# Snap4.net
KiCad netlist of a schematic drawn in Altium Designer
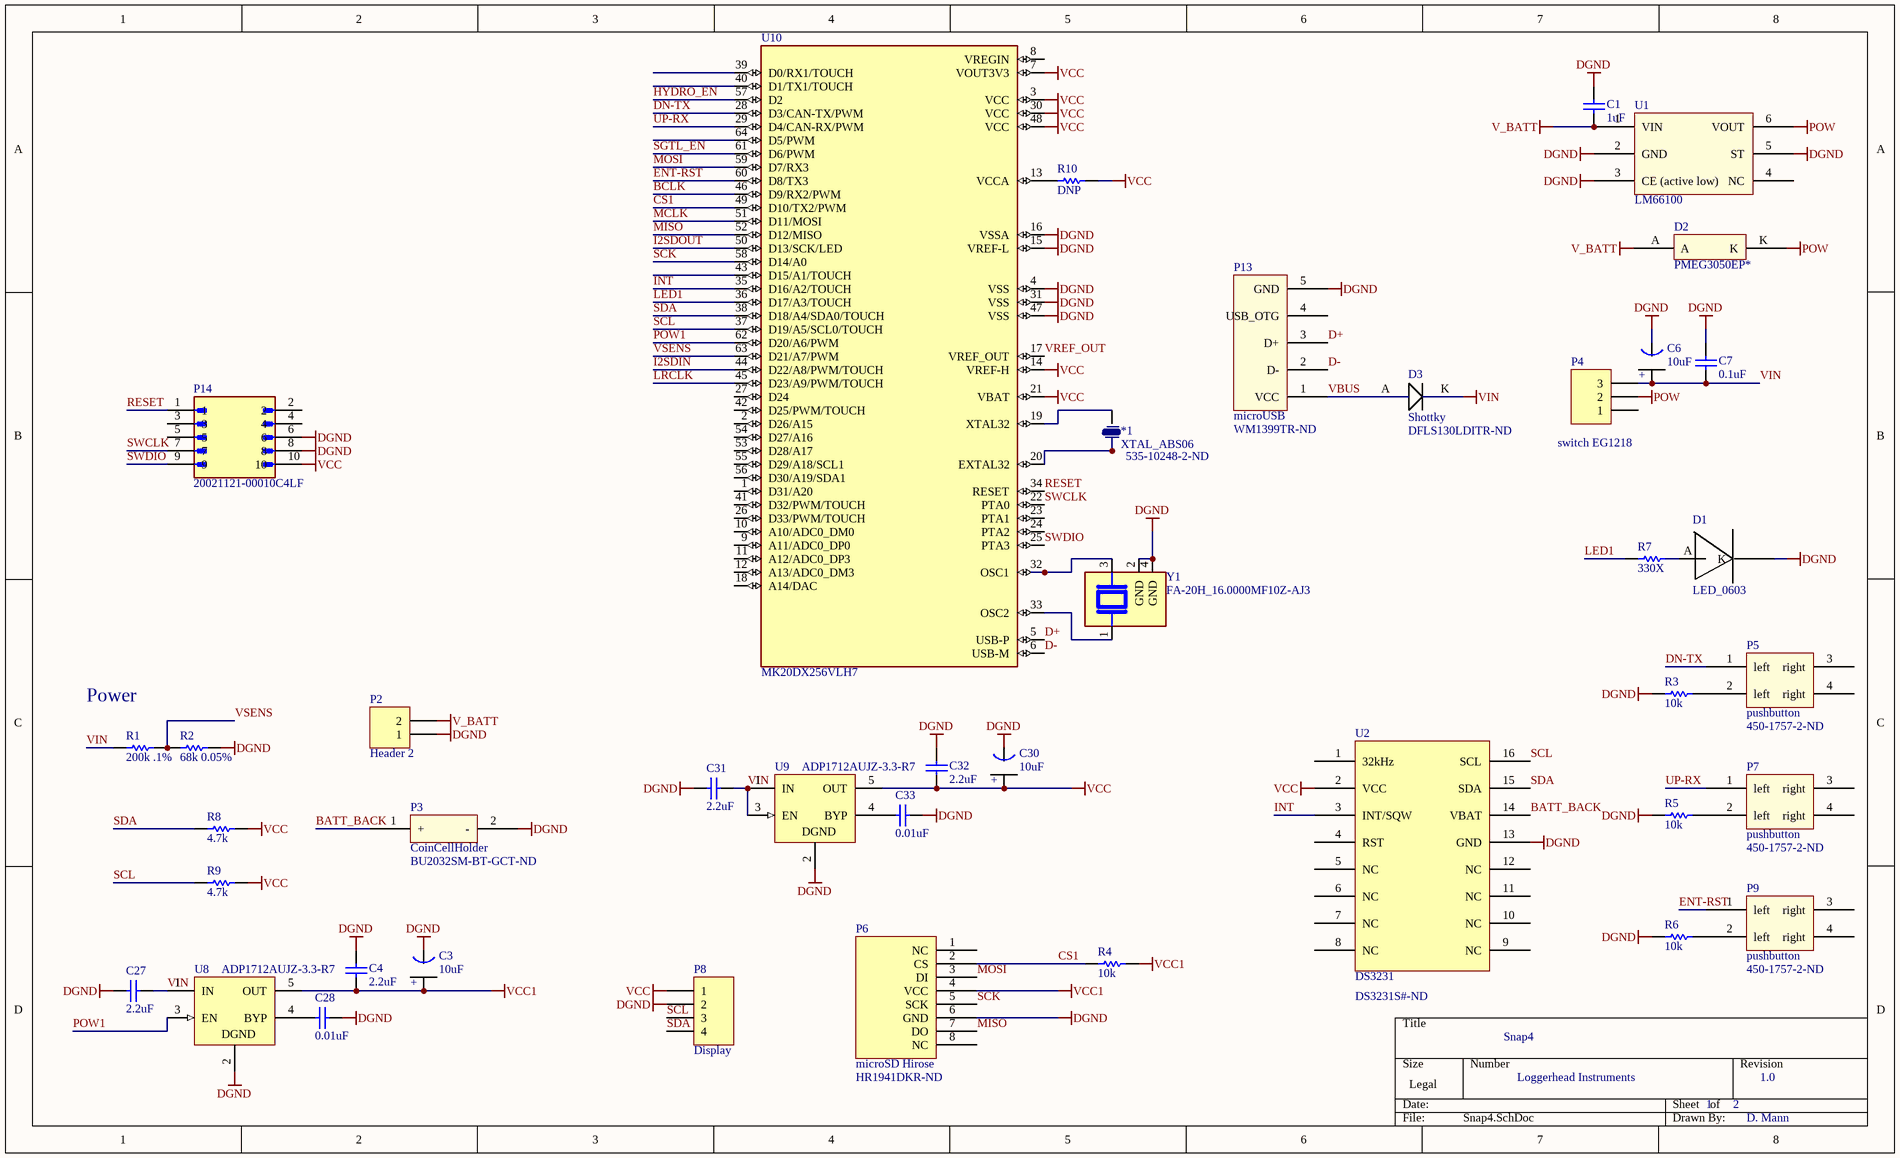
[diagram p0: Snap4.SchDoc]

(export (version "E")
  (design (tool "Eeschema 10.0.6"))
  (components
    (comp (ref "*1")
      (value "XTAL_ABS06")
      (footprint "XTAL-ABS06")
      (fields (field (name "SUPPLIER PART NUMBER 1") "535-10248-2-ND"))
      (libsource (lib "Loggerhead") (part "XTAL_ABS06"))
    )
    (comp (ref "C1")
      (value "1uF")
      (footprint "0402")
      (description "Ceramic Chip Capacitor - Standard")
      (fields (field (name "PUBLISHER") "Altium Limited"))
      (libsource (lib "KEMET Chip Capacitor") (part "C0402"))
    )
    (comp (ref "C3") (value "10uF") (footprint "Tant0805") (libsource (lib "Loggerhead") (part "Tant0805")))
    (comp (ref "C4")
      (value "2.2uF")
      (footprint "0402")
      (description "Ceramic Chip Capacitor - Standard")
      (fields (field (name "PUBLISHER") "Altium Limited"))
      (libsource (lib "KEMET Chip Capacitor") (part "C0402"))
    )
    (comp (ref "C6") (value "10uF") (footprint "Tant0805") (libsource (lib "Loggerhead") (part "Tant0805")))
    (comp (ref "C7")
      (value "0.1uF")
      (footprint "0402")
      (description "Ceramic Chip Capacitor - Standard")
      (fields (field (name "PUBLISHER") "Altium Limited"))
      (libsource (lib "KEMET Chip Capacitor") (part "C0402"))
    )
    (comp (ref "C27")
      (value "2.2uF")
      (footprint "0402")
      (description "Ceramic Chip Capacitor - Standard")
      (fields (field (name "PUBLISHER") "Altium Limited"))
      (libsource (lib "KEMET Chip Capacitor") (part "C0402"))
    )
    (comp (ref "C28")
      (value "0.01uF")
      (footprint "0402")
      (description "Ceramic Chip Capacitor - Standard")
      (fields (field (name "PUBLISHER") "Altium Limited"))
      (libsource (lib "KEMET Chip Capacitor") (part "C0402"))
    )
    (comp (ref "C30") (value "10uF") (footprint "Tant0805") (libsource (lib "Loggerhead") (part "Tant0805")))
    (comp (ref "C31")
      (value "2.2uF")
      (footprint "0402")
      (description "Ceramic Chip Capacitor - Standard")
      (fields (field (name "PUBLISHER") "Altium Limited"))
      (libsource (lib "KEMET Chip Capacitor") (part "C0402"))
    )
    (comp (ref "C32")
      (value "2.2uF")
      (footprint "0402")
      (description "Ceramic Chip Capacitor - Standard")
      (fields (field (name "PUBLISHER") "Altium Limited"))
      (libsource (lib "KEMET Chip Capacitor") (part "C0402"))
    )
    (comp (ref "C33")
      (value "0.01uF")
      (footprint "0402")
      (description "Ceramic Chip Capacitor - Standard")
      (fields (field (name "PUBLISHER") "Altium Limited"))
      (libsource (lib "KEMET Chip Capacitor") (part "C0402"))
    )
    (comp (ref "D1")
      (value "LED_0603")
      (footprint "Diode0603")
      (libsource (lib "Loggerhead") (part "LED_0603"))
    )
    (comp (ref "D2")
      (value "PMEG3050EP*")
      (footprint "Diode_PMEG3050EP")
      (libsource (lib "Loggerhead") (part "Diode_PMEG3050EP"))
    )
    (comp (ref "D3")
      (value "Shottky")
      (footprint "DFLS130")
      (fields (field (name "SUPPLIER PART NUMBER 1") "DFLS130LDITR-ND"))
      (libsource (lib "Loggerhead") (part "DFLS130"))
    )
    (comp (ref "P2")
      (value "Header 2")
      (footprint "HDR1X2")
      (description "Header, 2-Pin")
      (fields (field (name "PUBLISHER") "Altium Limited"))
      (libsource (lib "Miscellaneous Connectors") (part "Header 2"))
    )
    (comp (ref "P3")
      (value "CoinCellHolder")
      (footprint "CoinCellHolder")
      (fields (field (name "SUPPLIER PART NUMBER 1") "BU2032SM-BT-GCT-ND"))
      (libsource (lib "Loggerhead") (part "CoinCellHolder"))
    )
    (comp (ref "P4")
      (value "switch EG1218")
      (footprint "HDR1X3")
      (description "Header, 3-Pin")
      (fields (field (name "PUBLISHER") "Altium Limited"))
      (libsource (lib "Miscellaneous Connectors") (part "Header 3"))
    )
    (comp (ref "P5")
      (value "pushbutton")
      (footprint "SOP4")
      (fields (field (name "SUPPLIER PART NUMBER 1") "450-1757-2-ND"))
      (libsource (lib "Loggerhead") (part "pushbutton"))
    )
    (comp (ref "P6")
      (value "microSD Hirose")
      (footprint "DM3D microSD")
      (fields (field (name "SUPPLIER PART NUMBER 1") "HR1941DKR-ND"))
      (libsource (lib "Loggerhead") (part "microSD Hirose"))
    )
    (comp (ref "P7")
      (value "pushbutton")
      (footprint "SOP4")
      (fields (field (name "SUPPLIER PART NUMBER 1") "450-1757-2-ND"))
      (libsource (lib "Loggerhead") (part "pushbutton"))
    )
    (comp (ref "P8")
      (value "Display")
      (footprint "HDR1X4")
      (description "Header, 4-Pin")
      (fields (field (name "PUBLISHER") "Altium Limited"))
      (libsource (lib "Miscellaneous Connectors") (part "Header 4"))
    )
    (comp (ref "P9")
      (value "pushbutton")
      (footprint "SOP4")
      (fields (field (name "SUPPLIER PART NUMBER 1") "450-1757-2-ND"))
      (libsource (lib "Loggerhead") (part "pushbutton"))
    )
    (comp (ref "P13")
      (value "microUSB")
      (footprint "microUSB-B")
      (fields (field (name "SUPPLIER PART NUMBER 1") "WM1399TR-ND"))
      (libsource (lib "Loggerhead") (part "microUSB-B"))
    )
    (comp (ref "P14")
      (value "20021121-00010C4LF")
      (footprint "AMPHENOL_20021121-00010C4LF")
      (fields (field (name "MF") "Amphenol ICC"))
      (libsource (lib "cortex_20021121-00010C4LF") (part "20021121-00010C4LF"))
    )
    (comp (ref "R1")
      (value "200k .1%")
      (footprint "3-0603")
      (fields (field (name "PUBLISHER") "Altium Limited"))
      (libsource (lib "Panasonic Resistor") (part "ERJ3RK"))
    )
    (comp (ref "R2")
      (value "68k 0.05%")
      (footprint "3-0603")
      (fields (field (name "PUBLISHER") "Altium Limited"))
      (libsource (lib "Panasonic Resistor") (part "ERJ3RK"))
    )
    (comp (ref "R3")
      (value "10k")
      (footprint "3-0603")
      (fields (field (name "PUBLISHER") "Altium Limited"))
      (libsource (lib "Panasonic Resistor") (part "ERJ3RK"))
    )
    (comp (ref "R4")
      (value "10k")
      (footprint "3-0603")
      (fields (field (name "PUBLISHER") "Altium Limited"))
      (libsource (lib "Panasonic Resistor") (part "ERJ3RK"))
    )
    (comp (ref "R5")
      (value "10k")
      (footprint "3-0603")
      (fields (field (name "PUBLISHER") "Altium Limited"))
      (libsource (lib "Panasonic Resistor") (part "ERJ3RK"))
    )
    (comp (ref "R6")
      (value "10k")
      (footprint "3-0603")
      (fields (field (name "PUBLISHER") "Altium Limited"))
      (libsource (lib "Panasonic Resistor") (part "ERJ3RK"))
    )
    (comp (ref "R7")
      (value "330X")
      (footprint "3-0603")
      (fields (field (name "PUBLISHER") "Altium Limited"))
      (libsource (lib "Panasonic Resistor") (part "ERJ3RK"))
    )
    (comp (ref "R8")
      (value "4.7k")
      (footprint "3-0603")
      (fields (field (name "PUBLISHER") "Altium Limited"))
      (libsource (lib "Panasonic Resistor") (part "ERJ3RK"))
    )
    (comp (ref "R9")
      (value "4.7k")
      (footprint "3-0603")
      (fields (field (name "PUBLISHER") "Altium Limited"))
      (libsource (lib "Panasonic Resistor") (part "ERJ3RK"))
    )
    (comp (ref "R10")
      (value "DNP")
      (footprint "3-0603")
      (fields (field (name "PUBLISHER") "Altium Limited"))
      (libsource (lib "Panasonic Resistor") (part "ERJ3RK"))
    )
    (comp (ref "U1") (value "LM66100") (footprint "SC-70-6") (libsource (lib "Loggerhead") (part "LM66100")))
    (comp (ref "U2")
      (value "DS3231")
      (footprint "DS3231")
      (fields (field (name "SUPPLIER PART NUMBER 1") "DS3231S#-ND"))
      (libsource (lib "Loggerhead") (part "DS3231"))
    )
    (comp (ref "U8")
      (value "ADP1712AUJZ-3.3-R7")
      (footprint "MF05A_N")
      (description "Micropower, 150mA Low-Noise Ultra Low-Dropout CMOS Voltage Regulator")
      (fields
        (field (name "PARTNUMBER") "LP3985IM5-3.3")
        (field (name "MANUFACTURER") "National Semiconductor")
        (field (name "PUBLISHER") "Altium Limited")
      )
      (libsource (lib "NSC LDO") (part "LP3985IM5-3.3"))
    )
    (comp (ref "U9")
      (value "ADP1712AUJZ-3.3-R7")
      (footprint "MF05A_N")
      (description "Micropower, 150mA Low-Noise Ultra Low-Dropout CMOS Voltage Regulator")
      (fields
        (field (name "PARTNUMBER") "LP3985IM5-3.3")
        (field (name "MANUFACTURER") "National Semiconductor")
        (field (name "PUBLISHER") "Altium Limited")
      )
      (libsource (lib "NSC LDO") (part "LP3985IM5-3.3"))
    )
    (comp (ref "U10")
      (value "MK20DX256VLH7")
      (footprint "QFP50P1200X1200X160-64N")
      (description "ARMÂ®CortexÂ®-M4Kinetis K20å¾®æŽ§åˆ¶å™¨IC 32ä½72MHz 256KBï¼ˆ256K x 8ï¼‰FLASH 64-LQFPï¼ˆ10x10ï¼‰")
      (fields (field (name "MF") "NXP USA"))
      (libsource (lib "MK20DX256VLH7") (part "MK20DX256VLH7"))
    )
    (comp (ref "Y1")
      (value "FA-20H_16.0000MF10Z-AJ3")
      (footprint "XTAL_FA-20H_16.0000MF10Z-AJ3")
      (description "16 MHz ±10ppm Crystal 8pF 80 Ohms 4-SMD, No Lead")
      (fields (field (name "MF") "EPSON") (field (name "MP") "FA-20H 16.0000MF10Z-AJ3"))
      (libsource (lib "FA-20H_16.0000MF10Z-AJ3") (part "FA-20H_16.0000MF10Z-AJ3"))
    )
  )
  (nets
    (net (code "1") (name "/BATT_BACK") (class "Default")
      (node (ref "P3") (pin "1") (pinfunction "+_1") (pintype "passive"))
      (node (ref "U2") (pin "14") (pinfunction "VBAT_14") (pintype "power_in"))
    )
    (net (code "2") (name "/BCLK") (class "Default")
      (node (ref "U10") (pin "46") (pinfunction "D9/RX2/PWM_46") (pintype "bidirectional"))
    )
    (net (code "3") (name "/CS1") (class "Default")
      (node (ref "P6") (pin "2") (pinfunction "CS_2") (pintype "passive"))
      (node (ref "R4") (pin "2") (pinfunction "2_2") (pintype "passive"))
      (node (ref "U10") (pin "49") (pinfunction "D10/TX2/PWM_49") (pintype "bidirectional"))
    )
    (net (code "4") (name "/D+") (class "Default")
      (node (ref "P13") (pin "3") (pinfunction "D+_3") (pintype "passive"))
      (node (ref "U10") (pin "5") (pinfunction "USB-P_5") (pintype "bidirectional"))
    )
    (net (code "5") (name "/D-") (class "Default")
      (node (ref "P13") (pin "2") (pinfunction "D-_2") (pintype "passive"))
      (node (ref "U10") (pin "6") (pinfunction "USB-M_6") (pintype "bidirectional"))
    )
    (net (code "6") (name "/DN-TX") (class "Default")
      (node (ref "P5") (pin "1") (pinfunction "left_1") (pintype "passive"))
      (node (ref "U10") (pin "28") (pinfunction "D3/CAN-TX/PWM_28") (pintype "bidirectional"))
    )
    (net (code "7") (name "/ENT-RST") (class "Default")
      (node (ref "P9") (pin "1") (pinfunction "left_1") (pintype "passive"))
      (node (ref "U10") (pin "60") (pinfunction "D8/TX3_60") (pintype "bidirectional"))
    )
    (net (code "8") (name "/HYDRO_EN") (class "Default")
      (node (ref "U10") (pin "57") (pinfunction "D2_57") (pintype "bidirectional"))
    )
    (net (code "9") (name "/I2SDIN") (class "Default")
      (node (ref "U10") (pin "44") (pinfunction "D22/A8/PWM/TOUCH_44") (pintype "bidirectional"))
    )
    (net (code "10") (name "/I2SDOUT") (class "Default")
      (node (ref "U10") (pin "50") (pinfunction "D13/SCK/LED_50") (pintype "bidirectional"))
    )
    (net (code "11") (name "/INT") (class "Default")
      (node (ref "U10") (pin "35") (pinfunction "D16/A2/TOUCH_35") (pintype "bidirectional"))
      (node (ref "U2") (pin "3") (pinfunction "INT/SQW_3") (pintype "passive"))
    )
    (net (code "12") (name "/LED1") (class "Default")
      (node (ref "R7") (pin "1") (pinfunction "1_1") (pintype "passive"))
      (node (ref "U10") (pin "36") (pinfunction "D17/A3/TOUCH_36") (pintype "bidirectional"))
    )
    (net (code "13") (name "/LRCLK") (class "Default")
      (node (ref "U10") (pin "45") (pinfunction "D23/A9/PWM/TOUCH_45") (pintype "bidirectional"))
    )
    (net (code "14") (name "/MCLK") (class "Default")
      (node (ref "U10") (pin "51") (pinfunction "D11/MOSI_51") (pintype "bidirectional"))
    )
    (net (code "15") (name "/MISO") (class "Default")
      (node (ref "P6") (pin "7") (pinfunction "DO_7") (pintype "passive"))
      (node (ref "U10") (pin "52") (pinfunction "D12/MISO_52") (pintype "bidirectional"))
    )
    (net (code "16") (name "/MOSI") (class "Default")
      (node (ref "P6") (pin "3") (pinfunction "DI_3") (pintype "passive"))
      (node (ref "U10") (pin "59") (pinfunction "D7/RX3_59") (pintype "bidirectional"))
    )
    (net (code "17") (name "/POW1") (class "Default")
      (node (ref "U10") (pin "62") (pinfunction "D20/A6/PWM_62") (pintype "bidirectional"))
      (node (ref "U8") (pin "3") (pinfunction "EN_3") (pintype "input"))
    )
    (net (code "18") (name "/RESET") (class "Default")
      (node (ref "P14") (pin "1") (pinfunction "1_1") (pintype "passive"))
      (node (ref "U10") (pin "34") (pinfunction "RESET_34") (pintype "bidirectional"))
    )
    (net (code "19") (name "/SCK") (class "Default")
      (node (ref "P6") (pin "5") (pinfunction "SCK_5") (pintype "passive"))
      (node (ref "U10") (pin "58") (pinfunction "D14/A0_58") (pintype "bidirectional"))
    )
    (net (code "20") (name "/SCL") (class "Default")
      (node (ref "P8") (pin "3") (pinfunction "3_3") (pintype "passive"))
      (node (ref "R9") (pin "1") (pinfunction "1_1") (pintype "passive"))
      (node (ref "U10") (pin "37") (pinfunction "D19/A5/SCL0/TOUCH_37") (pintype "bidirectional"))
      (node (ref "U2") (pin "16") (pinfunction "SCL_16") (pintype "passive"))
    )
    (net (code "21") (name "/SDA") (class "Default")
      (node (ref "P8") (pin "4") (pinfunction "4_4") (pintype "passive"))
      (node (ref "R8") (pin "1") (pinfunction "1_1") (pintype "passive"))
      (node (ref "U10") (pin "38") (pinfunction "D18/A4/SDA0/TOUCH_38") (pintype "bidirectional"))
      (node (ref "U2") (pin "15") (pinfunction "SDA_15") (pintype "passive"))
    )
    (net (code "22") (name "/SGTL_EN") (class "Default")
      (node (ref "U10") (pin "61") (pinfunction "D6/PWM_61") (pintype "bidirectional"))
    )
    (net (code "23") (name "/SWCLK") (class "Default")
      (node (ref "P14") (pin "7") (pinfunction "7_7") (pintype "passive"))
      (node (ref "U10") (pin "22") (pinfunction "PTA0_22") (pintype "bidirectional"))
    )
    (net (code "24") (name "/SWDIO") (class "Default")
      (node (ref "P14") (pin "9") (pinfunction "9_9") (pintype "passive"))
      (node (ref "U10") (pin "25") (pinfunction "PTA3_25") (pintype "bidirectional"))
    )
    (net (code "25") (name "/UP-RX") (class "Default")
      (node (ref "P7") (pin "1") (pinfunction "left_1") (pintype "passive"))
      (node (ref "U10") (pin "29") (pinfunction "D4/CAN-RX/PWM_29") (pintype "bidirectional"))
    )
    (net (code "26") (name "/VBUS") (class "Default")
      (node (ref "D3") (pin "A") (pintype "passive"))
      (node (ref "P13") (pin "1") (pinfunction "VCC_1") (pintype "passive"))
    )
    (net (code "27") (name "/VREF_OUT") (class "Default")
      (node (ref "U10") (pin "17") (pinfunction "VREF_OUT_17") (pintype "bidirectional"))
    )
    (net (code "28") (name "/VSENS") (class "Default")
      (node (ref "R1") (pin "1") (pinfunction "1_1") (pintype "passive"))
      (node (ref "R2") (pin "2") (pinfunction "2_2") (pintype "passive"))
      (node (ref "U10") (pin "63") (pinfunction "D21/A7/PWM_63") (pintype "bidirectional"))
    )
    (net (code "29") (name "DGND") (class "Default")
      (node (ref "C1") (pin "1") (pinfunction "1_1") (pintype "passive"))
      (node (ref "C27") (pin "2") (pinfunction "2_2") (pintype "passive"))
      (node (ref "C28") (pin "2") (pinfunction "2_2") (pintype "passive"))
      (node (ref "C3") (pin "1") (pinfunction "GND_1") (pintype "passive"))
      (node (ref "C30") (pin "1") (pinfunction "GND_1") (pintype "passive"))
      (node (ref "C31") (pin "2") (pinfunction "2_2") (pintype "passive"))
      (node (ref "C32") (pin "2") (pinfunction "2_2") (pintype "passive"))
      (node (ref "C33") (pin "2") (pinfunction "2_2") (pintype "passive"))
      (node (ref "C4") (pin "2") (pinfunction "2_2") (pintype "passive"))
      (node (ref "C6") (pin "1") (pinfunction "GND_1") (pintype "passive"))
      (node (ref "C7") (pin "2") (pinfunction "2_2") (pintype "passive"))
      (node (ref "D1") (pin "K") (pinfunction "K_K") (pintype "passive"))
      (node (ref "P13") (pin "5") (pinfunction "GND_5") (pintype "passive"))
      (node (ref "P14") (pin "6") (pinfunction "6_6") (pintype "passive"))
      (node (ref "P14") (pin "8") (pinfunction "8_8") (pintype "passive"))
      (node (ref "P2") (pin "1") (pinfunction "1_1") (pintype "passive"))
      (node (ref "P3") (pin "2") (pinfunction "-_2") (pintype "passive"))
      (node (ref "P6") (pin "6") (pinfunction "GND_6") (pintype "passive"))
      (node (ref "P8") (pin "2") (pinfunction "2_2") (pintype "passive"))
      (node (ref "R2") (pin "1") (pinfunction "1_1") (pintype "passive"))
      (node (ref "R3") (pin "2") (pinfunction "2_2") (pintype "passive"))
      (node (ref "R5") (pin "2") (pinfunction "2_2") (pintype "passive"))
      (node (ref "R6") (pin "2") (pinfunction "2_2") (pintype "passive"))
      (node (ref "U1") (pin "2") (pinfunction "GND_2") (pintype "passive"))
      (node (ref "U1") (pin "3") (pinfunction "CE_(active_low)_3") (pintype "passive"))
      (node (ref "U1") (pin "5") (pinfunction "ST_5") (pintype "passive"))
      (node (ref "U10") (pin "15") (pinfunction "VREF-L_15") (pintype "bidirectional"))
      (node (ref "U10") (pin "16") (pinfunction "VSSA_16") (pintype "bidirectional"))
      (node (ref "U10") (pin "31") (pinfunction "VSS_31") (pintype "bidirectional"))
      (node (ref "U10") (pin "4") (pinfunction "VSS_4") (pintype "bidirectional"))
      (node (ref "U10") (pin "47") (pinfunction "VSS_47") (pintype "bidirectional"))
      (node (ref "U2") (pin "13") (pinfunction "GND_13") (pintype "passive"))
      (node (ref "U8") (pin "2") (pinfunction "GND_2") (pintype "power_in"))
      (node (ref "U9") (pin "2") (pinfunction "GND_2") (pintype "power_in"))
      (node (ref "Y1") (pin "2") (pinfunction "GND_2") (pintype "power_in"))
      (node (ref "Y1") (pin "4") (pinfunction "GND_4") (pintype "power_in"))
    )
    (net (code "30") (name "Net-(D1-PadA)") (class "Default")
      (node (ref "D1") (pin "A") (pinfunction "A_A") (pintype "passive"))
      (node (ref "R7") (pin "2") (pinfunction "2_2") (pintype "passive"))
    )
    (net (code "31") (name "Net-(P5-left-Pad2)") (class "Default")
      (node (ref "P5") (pin "2") (pinfunction "left_2") (pintype "passive"))
      (node (ref "R3") (pin "1") (pinfunction "1_1") (pintype "passive"))
    )
    (net (code "32") (name "Net-(P7-left-Pad2)") (class "Default")
      (node (ref "P7") (pin "2") (pinfunction "left_2") (pintype "passive"))
      (node (ref "R5") (pin "1") (pinfunction "1_1") (pintype "passive"))
    )
    (net (code "33") (name "Net-(P9-left-Pad2)") (class "Default")
      (node (ref "P9") (pin "2") (pinfunction "left_2") (pintype "passive"))
      (node (ref "R6") (pin "1") (pinfunction "1_1") (pintype "passive"))
    )
    (net (code "34") (name "Net-(U8-BYP)") (class "Default")
      (node (ref "C28") (pin "1") (pinfunction "1_1") (pintype "passive"))
      (node (ref "U8") (pin "4") (pinfunction "BYP_4") (pintype "passive"))
    )
    (net (code "35") (name "Net-(U9-BYP)") (class "Default")
      (node (ref "C33") (pin "1") (pinfunction "1_1") (pintype "passive"))
      (node (ref "U9") (pin "4") (pinfunction "BYP_4") (pintype "passive"))
    )
    (net (code "36") (name "Net-(U10-EXTAL32)") (class "Default")
      (node (ref "*1") (pin "1") (pinfunction "1_1") (pintype "passive"))
      (node (ref "U10") (pin "20") (pinfunction "EXTAL32_20") (pintype "bidirectional"))
    )
    (net (code "37") (name "Net-(U10-OSC1)") (class "Default")
      (node (ref "U10") (pin "32") (pinfunction "OSC1_32") (pintype "bidirectional"))
      (node (ref "Y1") (pin "3") (pinfunction "2_3") (pintype "passive"))
    )
    (net (code "38") (name "Net-(U10-OSC2)") (class "Default")
      (node (ref "U10") (pin "33") (pinfunction "OSC2_33") (pintype "bidirectional"))
      (node (ref "Y1") (pin "1") (pinfunction "1_1") (pintype "passive"))
    )
    (net (code "39") (name "Net-(U10-VCCA)") (class "Default")
      (node (ref "R10") (pin "1") (pinfunction "1_1") (pintype "passive"))
      (node (ref "U10") (pin "13") (pinfunction "VCCA_13") (pintype "bidirectional"))
    )
    (net (code "40") (name "Net-(U10-XTAL32)") (class "Default")
      (node (ref "*1") (pin "2") (pinfunction "2_2") (pintype "passive"))
      (node (ref "U10") (pin "19") (pinfunction "XTAL32_19") (pintype "bidirectional"))
    )
    (net (code "41") (name "POW") (class "Default")
      (node (ref "D2") (pin "K") (pinfunction "K_K") (pintype "passive"))
      (node (ref "P4") (pin "2") (pinfunction "2_2") (pintype "passive"))
      (node (ref "U1") (pin "6") (pinfunction "VOUT_6") (pintype "passive"))
    )
    (net (code "42") (name "VCC") (class "Default")
      (node (ref "C30") (pin "2") (pinfunction "+_2") (pintype "passive"))
      (node (ref "C32") (pin "1") (pinfunction "1_1") (pintype "passive"))
      (node (ref "P14") (pin "10") (pinfunction "10_10") (pintype "passive"))
      (node (ref "P8") (pin "1") (pinfunction "1_1") (pintype "passive"))
      (node (ref "R10") (pin "2") (pinfunction "2_2") (pintype "passive"))
      (node (ref "R8") (pin "2") (pinfunction "2_2") (pintype "passive"))
      (node (ref "R9") (pin "2") (pinfunction "2_2") (pintype "passive"))
      (node (ref "U10") (pin "14") (pinfunction "VREF-H_14") (pintype "bidirectional"))
      (node (ref "U10") (pin "21") (pinfunction "VBAT_21") (pintype "bidirectional"))
      (node (ref "U10") (pin "3") (pinfunction "VCC_3") (pintype "bidirectional"))
      (node (ref "U10") (pin "30") (pinfunction "VCC_30") (pintype "bidirectional"))
      (node (ref "U10") (pin "48") (pinfunction "VCC_48") (pintype "bidirectional"))
      (node (ref "U10") (pin "7") (pinfunction "VOUT3V3_7") (pintype "bidirectional"))
      (node (ref "U2") (pin "2") (pinfunction "VCC_2") (pintype "power_in"))
      (node (ref "U9") (pin "5") (pinfunction "OUT_5") (pintype "power_in"))
    )
    (net (code "43") (name "VCC1") (class "Default")
      (node (ref "C3") (pin "2") (pinfunction "+_2") (pintype "passive"))
      (node (ref "C4") (pin "1") (pinfunction "1_1") (pintype "passive"))
      (node (ref "P6") (pin "4") (pinfunction "VCC_4") (pintype "passive"))
      (node (ref "R4") (pin "1") (pinfunction "1_1") (pintype "passive"))
      (node (ref "U8") (pin "5") (pinfunction "OUT_5") (pintype "power_in"))
    )
    (net (code "44") (name "VIN") (class "Default")
      (node (ref "C27") (pin "1") (pinfunction "1_1") (pintype "passive"))
      (node (ref "C31") (pin "1") (pinfunction "1_1") (pintype "passive"))
      (node (ref "C6") (pin "2") (pinfunction "+_2") (pintype "passive"))
      (node (ref "C7") (pin "1") (pinfunction "1_1") (pintype "passive"))
      (node (ref "D3") (pin "K") (pintype "passive"))
      (node (ref "P4") (pin "3") (pinfunction "3_3") (pintype "passive"))
      (node (ref "R1") (pin "2") (pinfunction "2_2") (pintype "passive"))
      (node (ref "U8") (pin "1") (pinfunction "IN_1") (pintype "power_in"))
      (node (ref "U9") (pin "1") (pinfunction "IN_1") (pintype "power_in"))
      (node (ref "U9") (pin "3") (pinfunction "EN_3") (pintype "input"))
    )
    (net (code "45") (name "V_BATT") (class "Default")
      (node (ref "C1") (pin "2") (pinfunction "2_2") (pintype "passive"))
      (node (ref "D2") (pin "A") (pinfunction "A_A") (pintype "passive"))
      (node (ref "P2") (pin "2") (pinfunction "2_2") (pintype "passive"))
      (node (ref "U1") (pin "1") (pinfunction "VIN_1") (pintype "passive"))
    )
    (net (code "46") (name "unconnected-(P4-Pad1)") (class "Default")
      (node (ref "P4") (pin "1") (pinfunction "1_1") (pintype "passive"))
    )
    (net (code "47") (name "unconnected-(P5-right-Pad3)") (class "Default")
      (node (ref "P5") (pin "3") (pinfunction "right_3") (pintype "passive"))
    )
    (net (code "48") (name "unconnected-(P5-right-Pad4)") (class "Default")
      (node (ref "P5") (pin "4") (pinfunction "right_4") (pintype "passive"))
    )
    (net (code "49") (name "unconnected-(P6-NC-Pad1)") (class "Default")
      (node (ref "P6") (pin "1") (pinfunction "NC_1") (pintype "passive"))
    )
    (net (code "50") (name "unconnected-(P6-NC-Pad8)") (class "Default")
      (node (ref "P6") (pin "8") (pinfunction "NC_8") (pintype "passive"))
    )
    (net (code "51") (name "unconnected-(P7-right-Pad3)") (class "Default")
      (node (ref "P7") (pin "3") (pinfunction "right_3") (pintype "passive"))
    )
    (net (code "52") (name "unconnected-(P7-right-Pad4)") (class "Default")
      (node (ref "P7") (pin "4") (pinfunction "right_4") (pintype "passive"))
    )
    (net (code "53") (name "unconnected-(P9-right-Pad3)") (class "Default")
      (node (ref "P9") (pin "3") (pinfunction "right_3") (pintype "passive"))
    )
    (net (code "54") (name "unconnected-(P9-right-Pad4)") (class "Default")
      (node (ref "P9") (pin "4") (pinfunction "right_4") (pintype "passive"))
    )
    (net (code "55") (name "unconnected-(P13-USB_OTG-Pad4)") (class "Default")
      (node (ref "P13") (pin "4") (pinfunction "USB_OTG_4") (pintype "passive"))
    )
    (net (code "56") (name "unconnected-(P14-Pad2)") (class "Default")
      (node (ref "P14") (pin "2") (pinfunction "2_2") (pintype "passive"))
    )
    (net (code "57") (name "unconnected-(P14-Pad3)") (class "Default")
      (node (ref "P14") (pin "3") (pinfunction "3_3") (pintype "passive"))
    )
    (net (code "58") (name "unconnected-(P14-Pad4)") (class "Default")
      (node (ref "P14") (pin "4") (pinfunction "4_4") (pintype "passive"))
    )
    (net (code "59") (name "unconnected-(P14-Pad5)") (class "Default")
      (node (ref "P14") (pin "5") (pinfunction "5_5") (pintype "passive"))
    )
    (net (code "60") (name "unconnected-(U1-NC-Pad4)") (class "Default")
      (node (ref "U1") (pin "4") (pinfunction "NC_4") (pintype "passive"))
    )
    (net (code "61") (name "unconnected-(U2-32kHz-Pad1)") (class "Default")
      (node (ref "U2") (pin "1") (pinfunction "32kHz_1") (pintype "passive"))
    )
    (net (code "62") (name "unconnected-(U2-NC-Pad5)") (class "Default")
      (node (ref "U2") (pin "5") (pinfunction "NC_5") (pintype "passive"))
    )
    (net (code "63") (name "unconnected-(U2-NC-Pad6)") (class "Default")
      (node (ref "U2") (pin "6") (pinfunction "NC_6") (pintype "passive"))
    )
    (net (code "64") (name "unconnected-(U2-NC-Pad7)") (class "Default")
      (node (ref "U2") (pin "7") (pinfunction "NC_7") (pintype "passive"))
    )
    (net (code "65") (name "unconnected-(U2-NC-Pad8)") (class "Default")
      (node (ref "U2") (pin "8") (pinfunction "NC_8") (pintype "passive"))
    )
    (net (code "66") (name "unconnected-(U2-NC-Pad9)") (class "Default")
      (node (ref "U2") (pin "9") (pinfunction "NC_9") (pintype "passive"))
    )
    (net (code "67") (name "unconnected-(U2-NC-Pad10)") (class "Default")
      (node (ref "U2") (pin "10") (pinfunction "NC_10") (pintype "passive"))
    )
    (net (code "68") (name "unconnected-(U2-NC-Pad11)") (class "Default")
      (node (ref "U2") (pin "11") (pinfunction "NC_11") (pintype "passive"))
    )
    (net (code "69") (name "unconnected-(U2-NC-Pad12)") (class "Default")
      (node (ref "U2") (pin "12") (pinfunction "NC_12") (pintype "passive"))
    )
    (net (code "70") (name "unconnected-(U2-RST-Pad4)") (class "Default")
      (node (ref "U2") (pin "4") (pinfunction "RST_4") (pintype "passive"))
    )
    (net (code "71") (name "unconnected-(U10-A10{slash}ADC0_DM0-Pad10)") (class "Default")
      (node (ref "U10") (pin "10") (pinfunction "A10/ADC0_DM0_10") (pintype "bidirectional"))
    )
    (net (code "72") (name "unconnected-(U10-A11{slash}ADC0_DP0-Pad9)") (class "Default")
      (node (ref "U10") (pin "9") (pinfunction "A11/ADC0_DP0_9") (pintype "bidirectional"))
    )
    (net (code "73") (name "unconnected-(U10-A12{slash}ADC0_DP3-Pad11)") (class "Default")
      (node (ref "U10") (pin "11") (pinfunction "A12/ADC0_DP3_11") (pintype "bidirectional"))
    )
    (net (code "74") (name "unconnected-(U10-A13{slash}ADC0_DM3-Pad12)") (class "Default")
      (node (ref "U10") (pin "12") (pinfunction "A13/ADC0_DM3_12") (pintype "bidirectional"))
    )
    (net (code "75") (name "unconnected-(U10-A14{slash}DAC-Pad18)") (class "Default")
      (node (ref "U10") (pin "18") (pinfunction "A14/DAC_18") (pintype "bidirectional"))
    )
    (net (code "76") (name "unconnected-(U10-D0{slash}RX1{slash}TOUCH-Pad39)") (class "Default")
      (node (ref "U10") (pin "39") (pinfunction "D0/RX1/TOUCH_39") (pintype "bidirectional"))
    )
    (net (code "77") (name "unconnected-(U10-D1{slash}TX1{slash}TOUCH-Pad40)") (class "Default")
      (node (ref "U10") (pin "40") (pinfunction "D1/TX1/TOUCH_40") (pintype "bidirectional"))
    )
    (net (code "78") (name "unconnected-(U10-D5{slash}PWM-Pad64)") (class "Default")
      (node (ref "U10") (pin "64") (pinfunction "D5/PWM_64") (pintype "bidirectional"))
    )
    (net (code "79") (name "unconnected-(U10-D15{slash}A1{slash}TOUCH-Pad43)") (class "Default")
      (node (ref "U10") (pin "43") (pinfunction "D15/A1/TOUCH_43") (pintype "bidirectional"))
    )
    (net (code "80") (name "unconnected-(U10-D24-Pad27)") (class "Default")
      (node (ref "U10") (pin "27") (pinfunction "D24_27") (pintype "bidirectional"))
    )
    (net (code "81") (name "unconnected-(U10-D25{slash}PWM{slash}TOUCH-Pad42)") (class "Default")
      (node (ref "U10") (pin "42") (pinfunction "D25/PWM/TOUCH_42") (pintype "bidirectional"))
    )
    (net (code "82") (name "unconnected-(U10-D26{slash}A15-Pad2)") (class "Default")
      (node (ref "U10") (pin "2") (pinfunction "D26/A15_2") (pintype "bidirectional"))
    )
    (net (code "83") (name "unconnected-(U10-D27{slash}A16-Pad54)") (class "Default")
      (node (ref "U10") (pin "54") (pinfunction "D27/A16_54") (pintype "bidirectional"))
    )
    (net (code "84") (name "unconnected-(U10-D28{slash}A17-Pad53)") (class "Default")
      (node (ref "U10") (pin "53") (pinfunction "D28/A17_53") (pintype "bidirectional"))
    )
    (net (code "85") (name "unconnected-(U10-D29{slash}A18{slash}SCL1-Pad55)") (class "Default")
      (node (ref "U10") (pin "55") (pinfunction "D29/A18/SCL1_55") (pintype "bidirectional"))
    )
    (net (code "86") (name "unconnected-(U10-D30{slash}A19{slash}SDA1-Pad56)") (class "Default")
      (node (ref "U10") (pin "56") (pinfunction "D30/A19/SDA1_56") (pintype "bidirectional"))
    )
    (net (code "87") (name "unconnected-(U10-D31{slash}A20-Pad1)") (class "Default")
      (node (ref "U10") (pin "1") (pinfunction "D31/A20_1") (pintype "bidirectional"))
    )
    (net (code "88") (name "unconnected-(U10-D32{slash}PWM{slash}TOUCH-Pad41)") (class "Default")
      (node (ref "U10") (pin "41") (pinfunction "D32/PWM/TOUCH_41") (pintype "bidirectional"))
    )
    (net (code "89") (name "unconnected-(U10-D33{slash}PWM{slash}TOUCH-Pad26)") (class "Default")
      (node (ref "U10") (pin "26") (pinfunction "D33/PWM/TOUCH_26") (pintype "bidirectional"))
    )
    (net (code "90") (name "unconnected-(U10-PTA1-Pad23)") (class "Default")
      (node (ref "U10") (pin "23") (pinfunction "PTA1_23") (pintype "bidirectional"))
    )
    (net (code "91") (name "unconnected-(U10-PTA2-Pad24)") (class "Default")
      (node (ref "U10") (pin "24") (pinfunction "PTA2_24") (pintype "bidirectional"))
    )
    (net (code "92") (name "unconnected-(U10-VREGIN-Pad8)") (class "Default")
      (node (ref "U10") (pin "8") (pinfunction "VREGIN_8") (pintype "bidirectional"))
    )
  )
)
